# test1.net
KiCad netlist of a schematic drawn in EAGLE
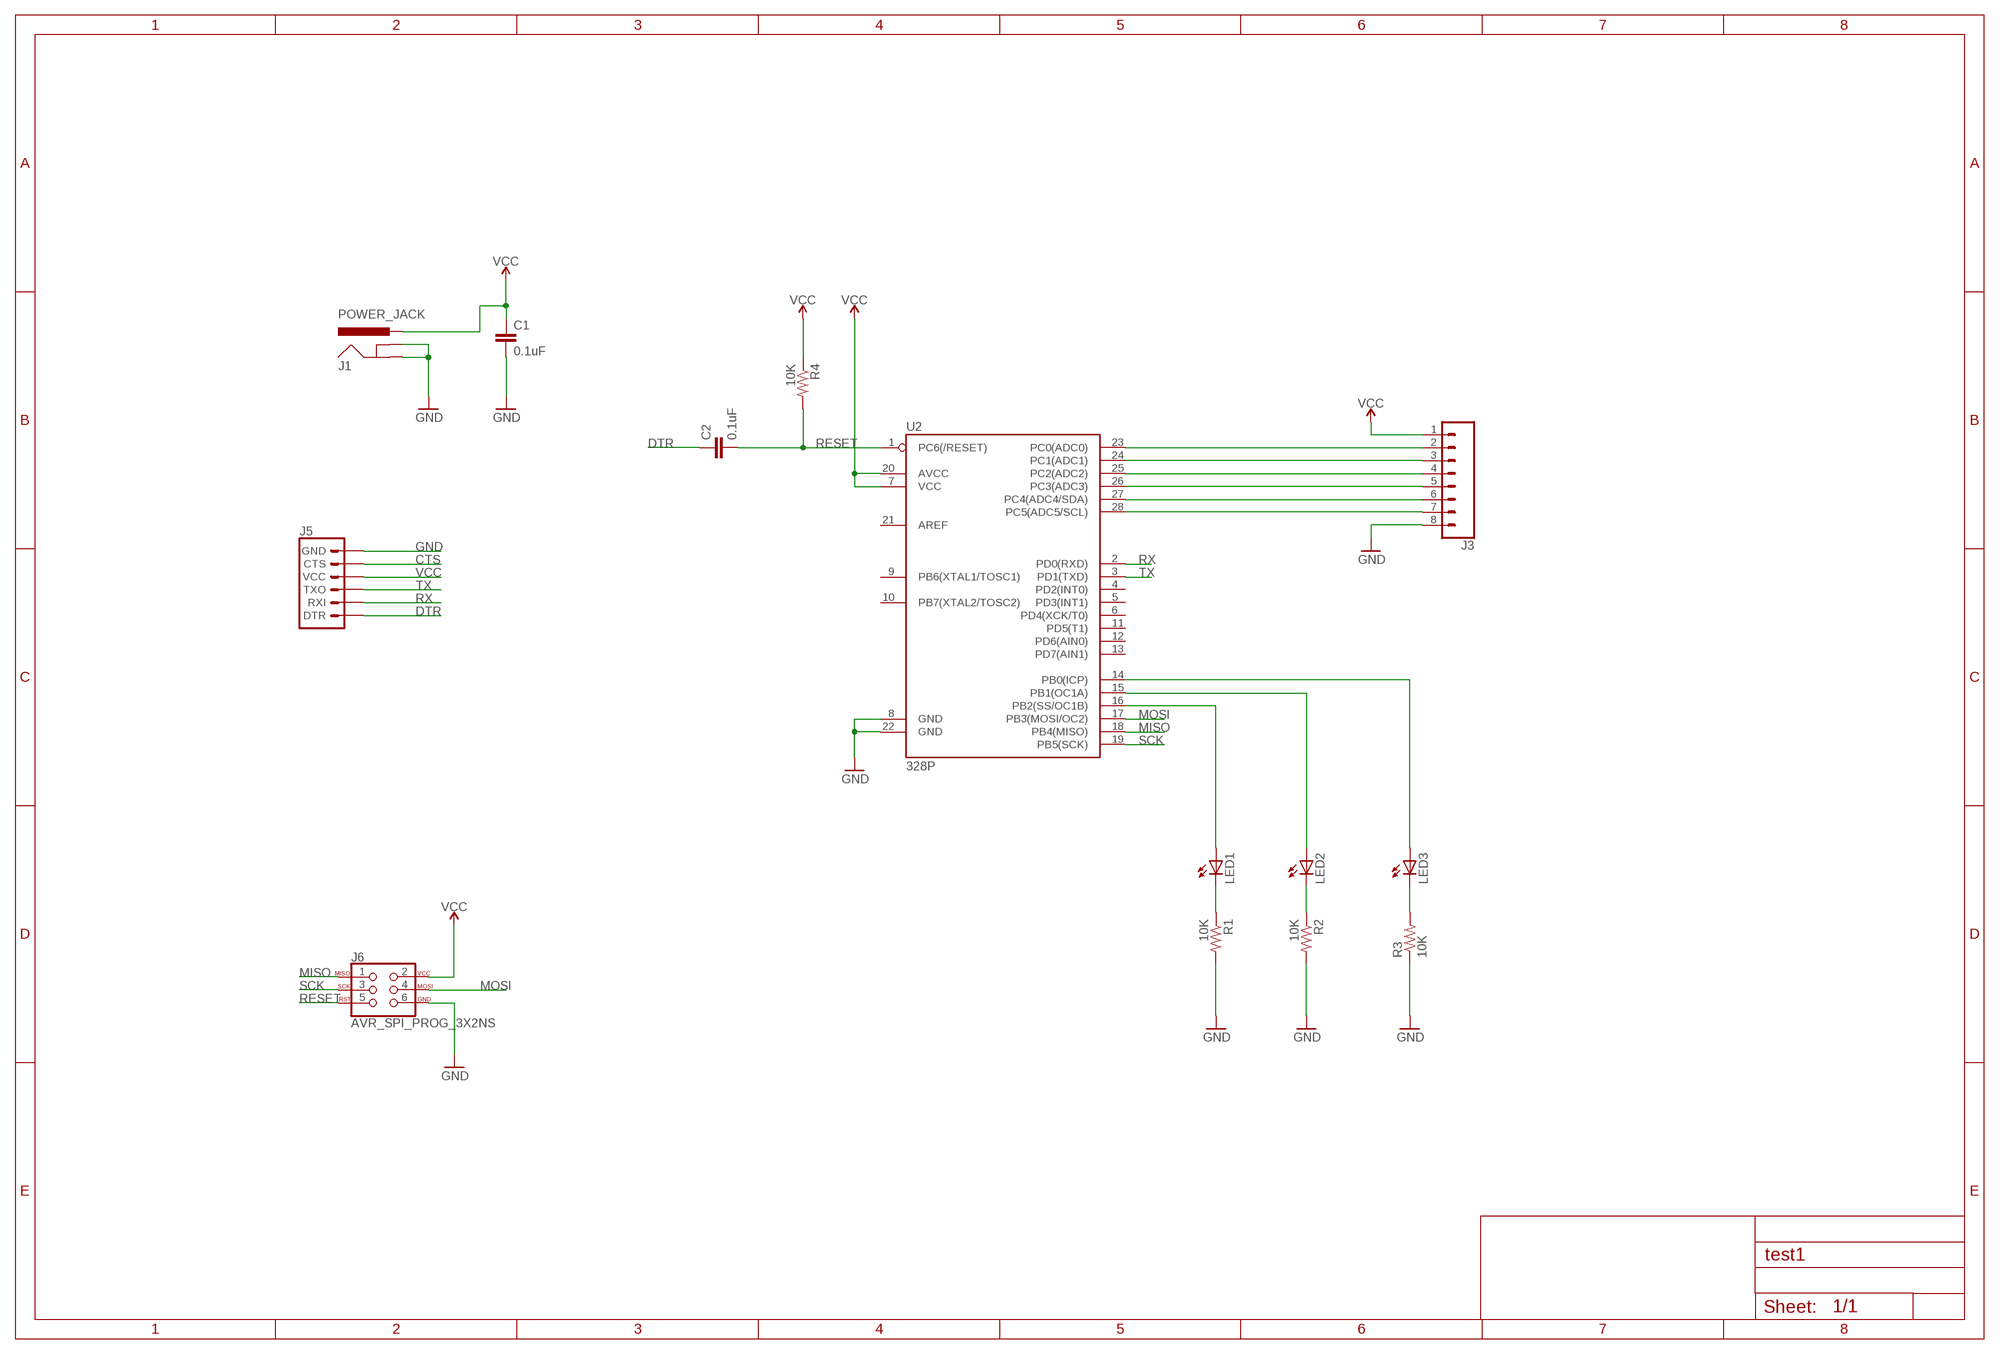
[diagram p0: schematic, sheet 1]

(export (version "E")
  (design (tool "Eeschema 10.0.6"))
  (components
    (comp (ref "C1")
      (value "0.1uF")
      (footprint "eagle-import:0402-CAP")
      (libsource (lib "eagle-import") (part ".1UF-CER"))
    )
    (comp (ref "C2")
      (value "0.1uF")
      (footprint "eagle-import:0402-CAP")
      (libsource (lib "eagle-import") (part ".1UF-CER"))
    )
    (comp (ref "J1")
      (value "POWER_JACK")
      (footprint "eagle-import:POWER_JACK_PTH")
      (libsource (lib "eagle-import") (part "POWER_JACK"))
    )
    (comp (ref "J3")
      (value "CONN_08\"")
      (footprint "eagle-import:1X08")
      (libsource (lib "eagle-import") (part "CONN_08{dblquote}"))
    )
    (comp (ref "J5")
      (value "6_PIN_SERIAL_TARGET")
      (footprint "eagle-import:1X06")
      (libsource (lib "eagle-import") (part "6_PIN_SERIAL_TARGET"))
    )
    (comp (ref "J6")
      (value "AVR_SPI_PROG_3X2NS")
      (footprint "eagle-import:2X3-NS")
      (libsource (lib "eagle-import") (part "AVR_SPI_PROG_3X2NS"))
    )
    (comp (ref "LED1")
      (value "LED5MM")
      (footprint "eagle-import:LED5MM")
      (libsource (lib "eagle-import") (part "LED5MM"))
    )
    (comp (ref "LED2")
      (value "LED5MM")
      (footprint "eagle-import:LED5MM")
      (libsource (lib "eagle-import") (part "LED5MM"))
    )
    (comp (ref "LED3")
      (value "LED5MM")
      (footprint "eagle-import:LED5MM")
      (libsource (lib "eagle-import") (part "LED5MM"))
    )
    (comp (ref "R1")
      (value "10K")
      (footprint "eagle-import:M3216")
      (libsource (lib "eagle-import") (part "R-US_M3216"))
    )
    (comp (ref "R2")
      (value "10K")
      (footprint "eagle-import:M3216")
      (libsource (lib "eagle-import") (part "R-US_M3216"))
    )
    (comp (ref "R3")
      (value "10K")
      (footprint "eagle-import:M3216")
      (libsource (lib "eagle-import") (part "R-US_M3216"))
    )
    (comp (ref "R4")
      (value "10K")
      (footprint "eagle-import:M3216")
      (libsource (lib "eagle-import") (part "R-US_M3216"))
    )
    (comp (ref "U2")
      (value "328P")
      (footprint "eagle-import:DIP28")
      (libsource (lib "eagle-import") (part "ATMEGA328P_PDIP"))
    )
  )
  (nets
    (net (code "1") (name "/CTS") (class "Default")
      (node (ref "J5") (pin "5") (pinfunction "CTS_5") (pintype "passive"))
    )
    (net (code "2") (name "/DTR") (class "Default")
      (node (ref "C2") (pin "1") (pinfunction "1_1") (pintype "passive"))
      (node (ref "J5") (pin "1") (pinfunction "DTR_1") (pintype "passive"))
    )
    (net (code "3") (name "/MISO") (class "Default")
      (node (ref "J6") (pin "1") (pinfunction "1_1") (pintype "passive"))
      (node (ref "U2") (pin "18") (pinfunction "PB4(MISO)_18") (pintype "bidirectional"))
    )
    (net (code "4") (name "/MOSI") (class "Default")
      (node (ref "J6") (pin "4") (pinfunction "4_4") (pintype "passive"))
      (node (ref "U2") (pin "17") (pinfunction "PB3(MOSI/OC2)_17") (pintype "bidirectional"))
    )
    (net (code "5") (name "/RESET") (class "Default")
      (node (ref "C2") (pin "2") (pinfunction "2_2") (pintype "passive"))
      (node (ref "J6") (pin "5") (pinfunction "5_5") (pintype "passive"))
      (node (ref "R4") (pin "2") (pinfunction "2_2") (pintype "passive"))
      (node (ref "U2") (pin "1") (pinfunction "PC6(/RESET)_1") (pintype "bidirectional"))
    )
    (net (code "6") (name "/RX") (class "Default")
      (node (ref "J5") (pin "2") (pinfunction "RXI_2") (pintype "passive"))
      (node (ref "U2") (pin "2") (pinfunction "PD0(RXD)_2") (pintype "bidirectional"))
    )
    (net (code "7") (name "/SCK") (class "Default")
      (node (ref "J6") (pin "3") (pinfunction "3_3") (pintype "passive"))
      (node (ref "U2") (pin "19") (pinfunction "PB5(SCK)_19") (pintype "bidirectional"))
    )
    (net (code "8") (name "/TX") (class "Default")
      (node (ref "J5") (pin "3") (pinfunction "TXO_3") (pintype "passive"))
      (node (ref "U2") (pin "3") (pinfunction "PD1(TXD)_3") (pintype "bidirectional"))
    )
    (net (code "9") (name "GND") (class "Default")
      (node (ref "C1") (pin "2") (pinfunction "2_2") (pintype "passive"))
      (node (ref "J1") (pin "GND") (pinfunction "GND_GND") (pintype "bidirectional"))
      (node (ref "J1") (pin "GNDBREAK") (pinfunction "GNDBREAK_GNDBREAK") (pintype "bidirectional"))
      (node (ref "J3") (pin "8") (pinfunction "8_8") (pintype "passive"))
      (node (ref "J5") (pin "6") (pinfunction "GND_6") (pintype "passive"))
      (node (ref "J6") (pin "6") (pinfunction "6_6") (pintype "passive"))
      (node (ref "R1") (pin "2") (pinfunction "2_2") (pintype "passive"))
      (node (ref "R2") (pin "2") (pinfunction "2_2") (pintype "passive"))
      (node (ref "R3") (pin "1") (pinfunction "1_1") (pintype "passive"))
      (node (ref "U2") (pin "22") (pinfunction "GND_22") (pintype "bidirectional"))
      (node (ref "U2") (pin "8") (pinfunction "GND_8") (pintype "bidirectional"))
    )
    (net (code "10") (name "Net-(LED1-C)") (class "Default")
      (node (ref "LED1") (pin "K") (pinfunction "C_K") (pintype "passive"))
      (node (ref "R1") (pin "1") (pinfunction "1_1") (pintype "passive"))
    )
    (net (code "11") (name "Net-(LED2-C)") (class "Default")
      (node (ref "LED2") (pin "K") (pinfunction "C_K") (pintype "passive"))
      (node (ref "R2") (pin "1") (pinfunction "1_1") (pintype "passive"))
    )
    (net (code "12") (name "Net-(LED3-C)") (class "Default")
      (node (ref "LED3") (pin "K") (pinfunction "C_K") (pintype "passive"))
      (node (ref "R3") (pin "2") (pinfunction "2_2") (pintype "passive"))
    )
    (net (code "13") (name "Net-(U2-PB0(ICP))") (class "Default")
      (node (ref "LED3") (pin "A") (pinfunction "A_A") (pintype "passive"))
      (node (ref "U2") (pin "14") (pinfunction "PB0(ICP)_14") (pintype "bidirectional"))
    )
    (net (code "14") (name "Net-(U2-PB1(OC1A))") (class "Default")
      (node (ref "LED2") (pin "A") (pinfunction "A_A") (pintype "passive"))
      (node (ref "U2") (pin "15") (pinfunction "PB1(OC1A)_15") (pintype "bidirectional"))
    )
    (net (code "15") (name "Net-(U2-PB2(SS{slash}OC1B))") (class "Default")
      (node (ref "LED1") (pin "A") (pinfunction "A_A") (pintype "passive"))
      (node (ref "U2") (pin "16") (pinfunction "PB2(SS/OC1B)_16") (pintype "bidirectional"))
    )
    (net (code "16") (name "Net-(U2-PC0(ADC0))") (class "Default")
      (node (ref "J3") (pin "2") (pinfunction "2_2") (pintype "passive"))
      (node (ref "U2") (pin "23") (pinfunction "PC0(ADC0)_23") (pintype "bidirectional"))
    )
    (net (code "17") (name "Net-(U2-PC1(ADC1))") (class "Default")
      (node (ref "J3") (pin "3") (pinfunction "3_3") (pintype "passive"))
      (node (ref "U2") (pin "24") (pinfunction "PC1(ADC1)_24") (pintype "bidirectional"))
    )
    (net (code "18") (name "Net-(U2-PC2(ADC2))") (class "Default")
      (node (ref "J3") (pin "4") (pinfunction "4_4") (pintype "passive"))
      (node (ref "U2") (pin "25") (pinfunction "PC2(ADC2)_25") (pintype "bidirectional"))
    )
    (net (code "19") (name "Net-(U2-PC3(ADC3))") (class "Default")
      (node (ref "J3") (pin "5") (pinfunction "5_5") (pintype "passive"))
      (node (ref "U2") (pin "26") (pinfunction "PC3(ADC3)_26") (pintype "bidirectional"))
    )
    (net (code "20") (name "Net-(U2-PC4(ADC4{slash}SDA))") (class "Default")
      (node (ref "J3") (pin "6") (pinfunction "6_6") (pintype "passive"))
      (node (ref "U2") (pin "27") (pinfunction "PC4(ADC4/SDA)_27") (pintype "bidirectional"))
    )
    (net (code "21") (name "Net-(U2-PC5(ADC5{slash}SCL))") (class "Default")
      (node (ref "J3") (pin "7") (pinfunction "7_7") (pintype "passive"))
      (node (ref "U2") (pin "28") (pinfunction "PC5(ADC5/SCL)_28") (pintype "bidirectional"))
    )
    (net (code "22") (name "VCC") (class "Default")
      (node (ref "C1") (pin "1") (pinfunction "1_1") (pintype "passive"))
      (node (ref "J1") (pin "PWR") (pinfunction "PWR_PWR") (pintype "bidirectional"))
      (node (ref "J3") (pin "1") (pinfunction "1_1") (pintype "passive"))
      (node (ref "J5") (pin "4") (pinfunction "VCC_4") (pintype "passive"))
      (node (ref "J6") (pin "2") (pinfunction "2_2") (pintype "passive"))
      (node (ref "R4") (pin "1") (pinfunction "1_1") (pintype "passive"))
      (node (ref "U2") (pin "20") (pinfunction "AVCC_20") (pintype "bidirectional"))
      (node (ref "U2") (pin "7") (pinfunction "VCC_7") (pintype "bidirectional"))
    )
    (net (code "23") (name "unconnected-(U2-AREF-Pad21)") (class "Default")
      (node (ref "U2") (pin "21") (pinfunction "AREF_21") (pintype "bidirectional"))
    )
    (net (code "24") (name "unconnected-(U2-PB6(XTAL1{slash}TOSC1)-Pad9)") (class "Default")
      (node (ref "U2") (pin "9") (pinfunction "PB6(XTAL1/TOSC1)_9") (pintype "bidirectional"))
    )
    (net (code "25") (name "unconnected-(U2-PB7(XTAL2{slash}TOSC2)-Pad10)") (class "Default")
      (node (ref "U2") (pin "10") (pinfunction "PB7(XTAL2/TOSC2)_10") (pintype "bidirectional"))
    )
    (net (code "26") (name "unconnected-(U2-PD2(INT0)-Pad4)") (class "Default")
      (node (ref "U2") (pin "4") (pinfunction "PD2(INT0)_4") (pintype "bidirectional"))
    )
    (net (code "27") (name "unconnected-(U2-PD3(INT1)-Pad5)") (class "Default")
      (node (ref "U2") (pin "5") (pinfunction "PD3(INT1)_5") (pintype "bidirectional"))
    )
    (net (code "28") (name "unconnected-(U2-PD4(XCK{slash}T0)-Pad6)") (class "Default")
      (node (ref "U2") (pin "6") (pinfunction "PD4(XCK/T0)_6") (pintype "bidirectional"))
    )
    (net (code "29") (name "unconnected-(U2-PD5(T1)-Pad11)") (class "Default")
      (node (ref "U2") (pin "11") (pinfunction "PD5(T1)_11") (pintype "bidirectional"))
    )
    (net (code "30") (name "unconnected-(U2-PD6(AIN0)-Pad12)") (class "Default")
      (node (ref "U2") (pin "12") (pinfunction "PD6(AIN0)_12") (pintype "bidirectional"))
    )
    (net (code "31") (name "unconnected-(U2-PD7(AIN1)-Pad13)") (class "Default")
      (node (ref "U2") (pin "13") (pinfunction "PD7(AIN1)_13") (pintype "bidirectional"))
    )
  )
)
